# TCA_LP_FILTER.net
KiCad netlist of a schematic drawn in Altium Designer
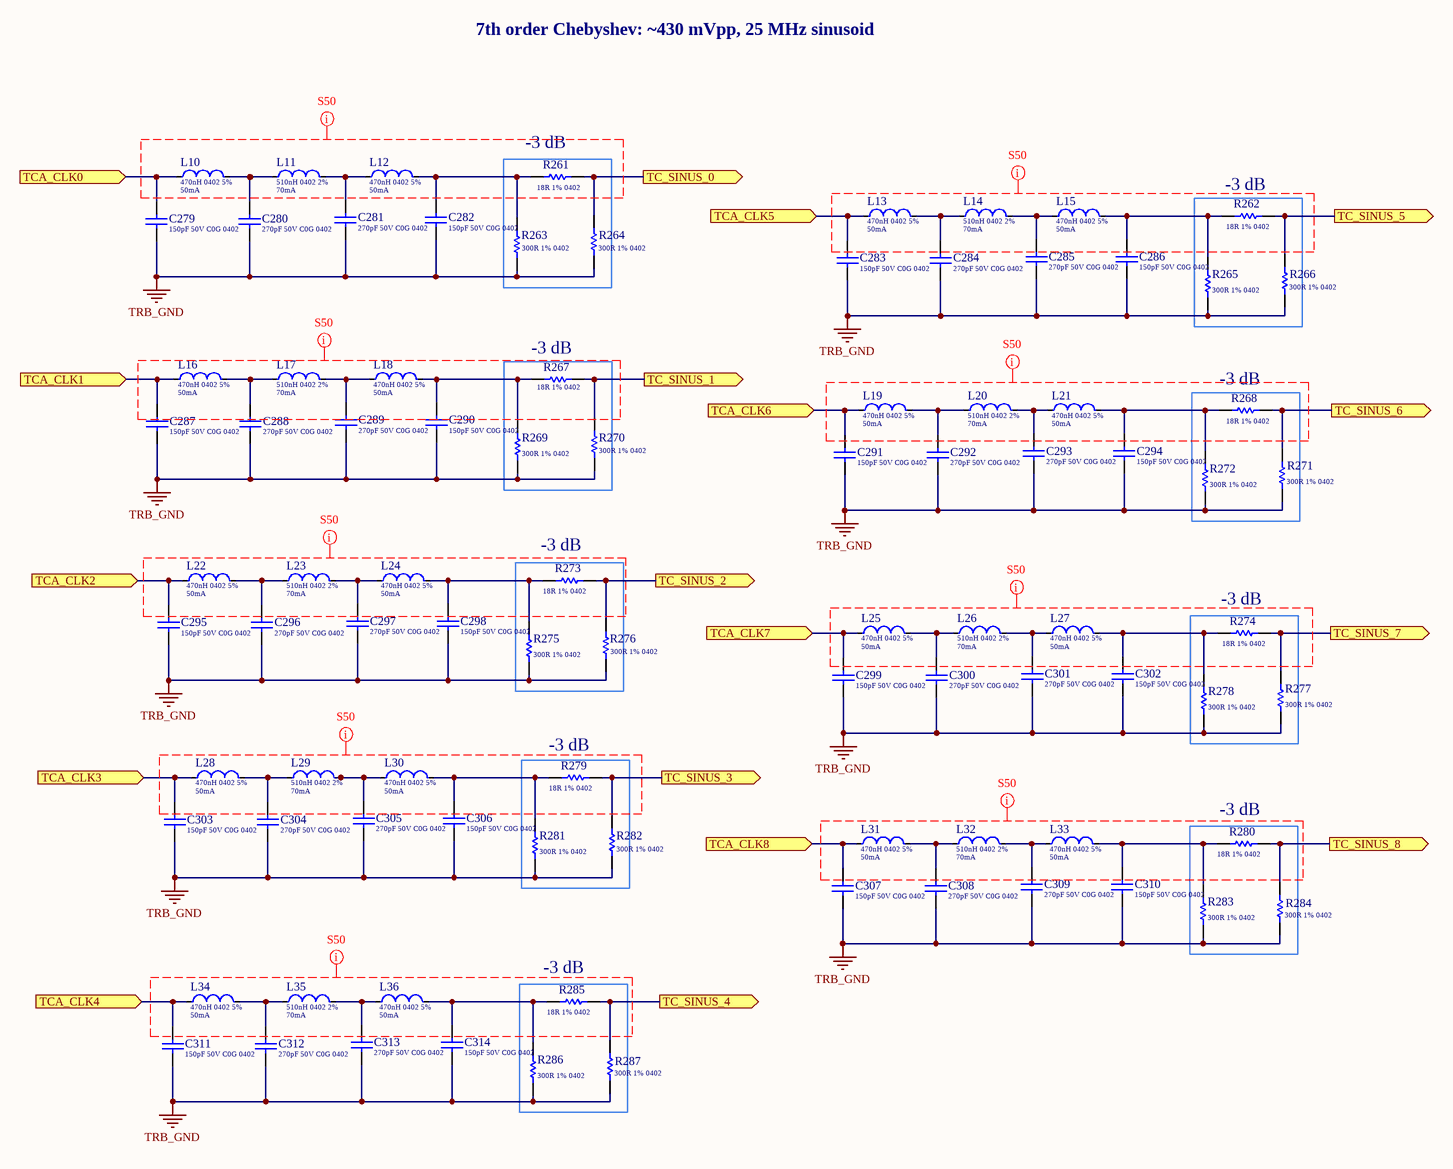
[diagram p0: TCA_LP_FILTER.SchDoc]

(export (version "E")
  (design (tool "Eeschema 10.0.6"))
  (components
    (comp (ref "C279")
      (value "Cap_TDK_CGA2B2C0G2A151J050BE_150pF")
      (footprint "Cap_TDK_CGA2B2C0G2A151J050BE_150pF")
      (description "CAP 150pF 50V C0G ±1% 0402 (1000 Metric) Thickness 1mm SMD")
      (fields (field (name "CAPACITANCE") "150pF 50V C0G 0402"))
      (libsource (lib "Cap_TDK_CGA2B2C0G2A151J050BE_150pF") (part "Cap_TDK_CGA2B2C0G2A151J050BE_150pF"))
    )
    (comp (ref "C280")
      (value "Cap_Murata_GCM1555C1H271FA16D_270pF")
      (footprint "Cap_Murata_GCM1555C1H271FA16D_270pF")
      (description "CAP 270pF 50V C0G ±1% 0402")
      (fields (field (name "CAPACITANCE") "270pF 50V C0G 0402"))
      (libsource (lib "Cap_Murata_GCM1555C1H271FA16D_270pF") (part "Cap_Murata_GCM1555C1H271FA16D_270pF"))
    )
    (comp (ref "C281")
      (value "Cap_Murata_GCM1555C1H271FA16D_270pF")
      (footprint "Cap_Murata_GCM1555C1H271FA16D_270pF")
      (description "CAP 270pF 50V C0G ±1% 0402")
      (fields (field (name "CAPACITANCE") "270pF 50V C0G 0402"))
      (libsource (lib "Cap_Murata_GCM1555C1H271FA16D_270pF") (part "Cap_Murata_GCM1555C1H271FA16D_270pF"))
    )
    (comp (ref "C282")
      (value "Cap_TDK_CGA2B2C0G2A151J050BE_150pF")
      (footprint "Cap_TDK_CGA2B2C0G2A151J050BE_150pF")
      (description "CAP 150pF 50V C0G ±1% 0402 (1000 Metric) Thickness 1mm SMD")
      (fields (field (name "CAPACITANCE") "150pF 50V C0G 0402"))
      (libsource (lib "Cap_TDK_CGA2B2C0G2A151J050BE_150pF") (part "Cap_TDK_CGA2B2C0G2A151J050BE_150pF"))
    )
    (comp (ref "C283")
      (value "Cap_TDK_CGA2B2C0G2A151J050BE_150pF")
      (footprint "Cap_TDK_CGA2B2C0G2A151J050BE_150pF")
      (description "CAP 150pF 50V C0G ±1% 0402 (1000 Metric) Thickness 1mm SMD")
      (fields (field (name "CAPACITANCE") "150pF 50V C0G 0402"))
      (libsource (lib "Cap_TDK_CGA2B2C0G2A151J050BE_150pF") (part "Cap_TDK_CGA2B2C0G2A151J050BE_150pF"))
    )
    (comp (ref "C284")
      (value "Cap_Murata_GCM1555C1H271FA16D_270pF")
      (footprint "Cap_Murata_GCM1555C1H271FA16D_270pF")
      (description "CAP 270pF 50V C0G ±1% 0402")
      (fields (field (name "CAPACITANCE") "270pF 50V C0G 0402"))
      (libsource (lib "Cap_Murata_GCM1555C1H271FA16D_270pF") (part "Cap_Murata_GCM1555C1H271FA16D_270pF"))
    )
    (comp (ref "C285")
      (value "Cap_Murata_GCM1555C1H271FA16D_270pF")
      (footprint "Cap_Murata_GCM1555C1H271FA16D_270pF")
      (description "CAP 270pF 50V C0G ±1% 0402")
      (fields (field (name "CAPACITANCE") "270pF 50V C0G 0402"))
      (libsource (lib "Cap_Murata_GCM1555C1H271FA16D_270pF") (part "Cap_Murata_GCM1555C1H271FA16D_270pF"))
    )
    (comp (ref "C286")
      (value "Cap_TDK_CGA2B2C0G2A151J050BE_150pF")
      (footprint "Cap_TDK_CGA2B2C0G2A151J050BE_150pF")
      (description "CAP 150pF 50V C0G ±1% 0402 (1000 Metric) Thickness 1mm SMD")
      (fields (field (name "CAPACITANCE") "150pF 50V C0G 0402"))
      (libsource (lib "Cap_TDK_CGA2B2C0G2A151J050BE_150pF") (part "Cap_TDK_CGA2B2C0G2A151J050BE_150pF"))
    )
    (comp (ref "C287")
      (value "Cap_TDK_CGA2B2C0G2A151J050BE_150pF")
      (footprint "Cap_TDK_CGA2B2C0G2A151J050BE_150pF")
      (description "CAP 150pF 50V C0G ±1% 0402 (1000 Metric) Thickness 1mm SMD")
      (fields (field (name "CAPACITANCE") "150pF 50V C0G 0402"))
      (libsource (lib "Cap_TDK_CGA2B2C0G2A151J050BE_150pF") (part "Cap_TDK_CGA2B2C0G2A151J050BE_150pF"))
    )
    (comp (ref "C288")
      (value "Cap_Murata_GCM1555C1H271FA16D_270pF")
      (footprint "Cap_Murata_GCM1555C1H271FA16D_270pF")
      (description "CAP 270pF 50V C0G ±1% 0402")
      (fields (field (name "CAPACITANCE") "270pF 50V C0G 0402"))
      (libsource (lib "Cap_Murata_GCM1555C1H271FA16D_270pF") (part "Cap_Murata_GCM1555C1H271FA16D_270pF"))
    )
    (comp (ref "C289")
      (value "Cap_Murata_GCM1555C1H271FA16D_270pF")
      (footprint "Cap_Murata_GCM1555C1H271FA16D_270pF")
      (description "CAP 270pF 50V C0G ±1% 0402")
      (fields (field (name "CAPACITANCE") "270pF 50V C0G 0402"))
      (libsource (lib "Cap_Murata_GCM1555C1H271FA16D_270pF") (part "Cap_Murata_GCM1555C1H271FA16D_270pF"))
    )
    (comp (ref "C290")
      (value "Cap_TDK_CGA2B2C0G2A151J050BE_150pF")
      (footprint "Cap_TDK_CGA2B2C0G2A151J050BE_150pF")
      (description "CAP 150pF 50V C0G ±1% 0402 (1000 Metric) Thickness 1mm SMD")
      (fields (field (name "CAPACITANCE") "150pF 50V C0G 0402"))
      (libsource (lib "Cap_TDK_CGA2B2C0G2A151J050BE_150pF") (part "Cap_TDK_CGA2B2C0G2A151J050BE_150pF"))
    )
    (comp (ref "C291")
      (value "Cap_TDK_CGA2B2C0G2A151J050BE_150pF")
      (footprint "Cap_TDK_CGA2B2C0G2A151J050BE_150pF")
      (description "CAP 150pF 50V C0G ±1% 0402 (1000 Metric) Thickness 1mm SMD")
      (fields (field (name "CAPACITANCE") "150pF 50V C0G 0402"))
      (libsource (lib "Cap_TDK_CGA2B2C0G2A151J050BE_150pF") (part "Cap_TDK_CGA2B2C0G2A151J050BE_150pF"))
    )
    (comp (ref "C292")
      (value "Cap_Murata_GCM1555C1H271FA16D_270pF")
      (footprint "Cap_Murata_GCM1555C1H271FA16D_270pF")
      (description "CAP 270pF 50V C0G ±1% 0402")
      (fields (field (name "CAPACITANCE") "270pF 50V C0G 0402"))
      (libsource (lib "Cap_Murata_GCM1555C1H271FA16D_270pF") (part "Cap_Murata_GCM1555C1H271FA16D_270pF"))
    )
    (comp (ref "C293")
      (value "Cap_Murata_GCM1555C1H271FA16D_270pF")
      (footprint "Cap_Murata_GCM1555C1H271FA16D_270pF")
      (description "CAP 270pF 50V C0G ±1% 0402")
      (fields (field (name "CAPACITANCE") "270pF 50V C0G 0402"))
      (libsource (lib "Cap_Murata_GCM1555C1H271FA16D_270pF") (part "Cap_Murata_GCM1555C1H271FA16D_270pF"))
    )
    (comp (ref "C294")
      (value "Cap_TDK_CGA2B2C0G2A151J050BE_150pF")
      (footprint "Cap_TDK_CGA2B2C0G2A151J050BE_150pF")
      (description "CAP 150pF 50V C0G ±1% 0402 (1000 Metric) Thickness 1mm SMD")
      (fields (field (name "CAPACITANCE") "150pF 50V C0G 0402"))
      (libsource (lib "Cap_TDK_CGA2B2C0G2A151J050BE_150pF") (part "Cap_TDK_CGA2B2C0G2A151J050BE_150pF"))
    )
    (comp (ref "C295")
      (value "Cap_TDK_CGA2B2C0G2A151J050BE_150pF")
      (footprint "Cap_TDK_CGA2B2C0G2A151J050BE_150pF")
      (description "CAP 150pF 50V C0G ±1% 0402 (1000 Metric) Thickness 1mm SMD")
      (fields (field (name "CAPACITANCE") "150pF 50V C0G 0402"))
      (libsource (lib "Cap_TDK_CGA2B2C0G2A151J050BE_150pF") (part "Cap_TDK_CGA2B2C0G2A151J050BE_150pF"))
    )
    (comp (ref "C296")
      (value "Cap_Murata_GCM1555C1H271FA16D_270pF")
      (footprint "Cap_Murata_GCM1555C1H271FA16D_270pF")
      (description "CAP 270pF 50V C0G ±1% 0402")
      (fields (field (name "CAPACITANCE") "270pF 50V C0G 0402"))
      (libsource (lib "Cap_Murata_GCM1555C1H271FA16D_270pF") (part "Cap_Murata_GCM1555C1H271FA16D_270pF"))
    )
    (comp (ref "C297")
      (value "Cap_Murata_GCM1555C1H271FA16D_270pF")
      (footprint "Cap_Murata_GCM1555C1H271FA16D_270pF")
      (description "CAP 270pF 50V C0G ±1% 0402")
      (fields (field (name "CAPACITANCE") "270pF 50V C0G 0402"))
      (libsource (lib "Cap_Murata_GCM1555C1H271FA16D_270pF") (part "Cap_Murata_GCM1555C1H271FA16D_270pF"))
    )
    (comp (ref "C298")
      (value "Cap_TDK_CGA2B2C0G2A151J050BE_150pF")
      (footprint "Cap_TDK_CGA2B2C0G2A151J050BE_150pF")
      (description "CAP 150pF 50V C0G ±1% 0402 (1000 Metric) Thickness 1mm SMD")
      (fields (field (name "CAPACITANCE") "150pF 50V C0G 0402"))
      (libsource (lib "Cap_TDK_CGA2B2C0G2A151J050BE_150pF") (part "Cap_TDK_CGA2B2C0G2A151J050BE_150pF"))
    )
    (comp (ref "C299")
      (value "Cap_TDK_CGA2B2C0G2A151J050BE_150pF")
      (footprint "Cap_TDK_CGA2B2C0G2A151J050BE_150pF")
      (description "CAP 150pF 50V C0G ±1% 0402 (1000 Metric) Thickness 1mm SMD")
      (fields (field (name "CAPACITANCE") "150pF 50V C0G 0402"))
      (libsource (lib "Cap_TDK_CGA2B2C0G2A151J050BE_150pF") (part "Cap_TDK_CGA2B2C0G2A151J050BE_150pF"))
    )
    (comp (ref "C300")
      (value "Cap_Murata_GCM1555C1H271FA16D_270pF")
      (footprint "Cap_Murata_GCM1555C1H271FA16D_270pF")
      (description "CAP 270pF 50V C0G ±1% 0402")
      (fields (field (name "CAPACITANCE") "270pF 50V C0G 0402"))
      (libsource (lib "Cap_Murata_GCM1555C1H271FA16D_270pF") (part "Cap_Murata_GCM1555C1H271FA16D_270pF"))
    )
    (comp (ref "C301")
      (value "Cap_Murata_GCM1555C1H271FA16D_270pF")
      (footprint "Cap_Murata_GCM1555C1H271FA16D_270pF")
      (description "CAP 270pF 50V C0G ±1% 0402")
      (fields (field (name "CAPACITANCE") "270pF 50V C0G 0402"))
      (libsource (lib "Cap_Murata_GCM1555C1H271FA16D_270pF") (part "Cap_Murata_GCM1555C1H271FA16D_270pF"))
    )
    (comp (ref "C302")
      (value "Cap_TDK_CGA2B2C0G2A151J050BE_150pF")
      (footprint "Cap_TDK_CGA2B2C0G2A151J050BE_150pF")
      (description "CAP 150pF 50V C0G ±1% 0402 (1000 Metric) Thickness 1mm SMD")
      (fields (field (name "CAPACITANCE") "150pF 50V C0G 0402"))
      (libsource (lib "Cap_TDK_CGA2B2C0G2A151J050BE_150pF") (part "Cap_TDK_CGA2B2C0G2A151J050BE_150pF"))
    )
    (comp (ref "C303")
      (value "Cap_TDK_CGA2B2C0G2A151J050BE_150pF")
      (footprint "Cap_TDK_CGA2B2C0G2A151J050BE_150pF")
      (description "CAP 150pF 50V C0G ±1% 0402 (1000 Metric) Thickness 1mm SMD")
      (fields (field (name "CAPACITANCE") "150pF 50V C0G 0402"))
      (libsource (lib "Cap_TDK_CGA2B2C0G2A151J050BE_150pF") (part "Cap_TDK_CGA2B2C0G2A151J050BE_150pF"))
    )
    (comp (ref "C304")
      (value "Cap_Murata_GCM1555C1H271FA16D_270pF")
      (footprint "Cap_Murata_GCM1555C1H271FA16D_270pF")
      (description "CAP 270pF 50V C0G ±1% 0402")
      (fields (field (name "CAPACITANCE") "270pF 50V C0G 0402"))
      (libsource (lib "Cap_Murata_GCM1555C1H271FA16D_270pF") (part "Cap_Murata_GCM1555C1H271FA16D_270pF"))
    )
    (comp (ref "C305")
      (value "Cap_Murata_GCM1555C1H271FA16D_270pF")
      (footprint "Cap_Murata_GCM1555C1H271FA16D_270pF")
      (description "CAP 270pF 50V C0G ±1% 0402")
      (fields (field (name "CAPACITANCE") "270pF 50V C0G 0402"))
      (libsource (lib "Cap_Murata_GCM1555C1H271FA16D_270pF") (part "Cap_Murata_GCM1555C1H271FA16D_270pF"))
    )
    (comp (ref "C306")
      (value "Cap_TDK_CGA2B2C0G2A151J050BE_150pF")
      (footprint "Cap_TDK_CGA2B2C0G2A151J050BE_150pF")
      (description "CAP 150pF 50V C0G ±1% 0402 (1000 Metric) Thickness 1mm SMD")
      (fields (field (name "CAPACITANCE") "150pF 50V C0G 0402"))
      (libsource (lib "Cap_TDK_CGA2B2C0G2A151J050BE_150pF") (part "Cap_TDK_CGA2B2C0G2A151J050BE_150pF"))
    )
    (comp (ref "C307")
      (value "Cap_TDK_CGA2B2C0G2A151J050BE_150pF")
      (footprint "Cap_TDK_CGA2B2C0G2A151J050BE_150pF")
      (description "CAP 150pF 50V C0G ±1% 0402 (1000 Metric) Thickness 1mm SMD")
      (fields (field (name "CAPACITANCE") "150pF 50V C0G 0402"))
      (libsource (lib "Cap_TDK_CGA2B2C0G2A151J050BE_150pF") (part "Cap_TDK_CGA2B2C0G2A151J050BE_150pF"))
    )
    (comp (ref "C308")
      (value "Cap_Murata_GCM1555C1H271FA16D_270pF")
      (footprint "Cap_Murata_GCM1555C1H271FA16D_270pF")
      (description "CAP 270pF 50V C0G ±1% 0402")
      (fields (field (name "CAPACITANCE") "270pF 50V C0G 0402"))
      (libsource (lib "Cap_Murata_GCM1555C1H271FA16D_270pF") (part "Cap_Murata_GCM1555C1H271FA16D_270pF"))
    )
    (comp (ref "C309")
      (value "Cap_Murata_GCM1555C1H271FA16D_270pF")
      (footprint "Cap_Murata_GCM1555C1H271FA16D_270pF")
      (description "CAP 270pF 50V C0G ±1% 0402")
      (fields (field (name "CAPACITANCE") "270pF 50V C0G 0402"))
      (libsource (lib "Cap_Murata_GCM1555C1H271FA16D_270pF") (part "Cap_Murata_GCM1555C1H271FA16D_270pF"))
    )
    (comp (ref "C310")
      (value "Cap_TDK_CGA2B2C0G2A151J050BE_150pF")
      (footprint "Cap_TDK_CGA2B2C0G2A151J050BE_150pF")
      (description "CAP 150pF 50V C0G ±1% 0402 (1000 Metric) Thickness 1mm SMD")
      (fields (field (name "CAPACITANCE") "150pF 50V C0G 0402"))
      (libsource (lib "Cap_TDK_CGA2B2C0G2A151J050BE_150pF") (part "Cap_TDK_CGA2B2C0G2A151J050BE_150pF"))
    )
    (comp (ref "C311")
      (value "Cap_TDK_CGA2B2C0G2A151J050BE_150pF")
      (footprint "Cap_TDK_CGA2B2C0G2A151J050BE_150pF")
      (description "CAP 150pF 50V C0G ±1% 0402 (1000 Metric) Thickness 1mm SMD")
      (fields (field (name "CAPACITANCE") "150pF 50V C0G 0402"))
      (libsource (lib "Cap_TDK_CGA2B2C0G2A151J050BE_150pF") (part "Cap_TDK_CGA2B2C0G2A151J050BE_150pF"))
    )
    (comp (ref "C312")
      (value "Cap_Murata_GCM1555C1H271FA16D_270pF")
      (footprint "Cap_Murata_GCM1555C1H271FA16D_270pF")
      (description "CAP 270pF 50V C0G ±1% 0402")
      (fields (field (name "CAPACITANCE") "270pF 50V C0G 0402"))
      (libsource (lib "Cap_Murata_GCM1555C1H271FA16D_270pF") (part "Cap_Murata_GCM1555C1H271FA16D_270pF"))
    )
    (comp (ref "C313")
      (value "Cap_Murata_GCM1555C1H271FA16D_270pF")
      (footprint "Cap_Murata_GCM1555C1H271FA16D_270pF")
      (description "CAP 270pF 50V C0G ±1% 0402")
      (fields (field (name "CAPACITANCE") "270pF 50V C0G 0402"))
      (libsource (lib "Cap_Murata_GCM1555C1H271FA16D_270pF") (part "Cap_Murata_GCM1555C1H271FA16D_270pF"))
    )
    (comp (ref "C314")
      (value "Cap_TDK_CGA2B2C0G2A151J050BE_150pF")
      (footprint "Cap_TDK_CGA2B2C0G2A151J050BE_150pF")
      (description "CAP 150pF 50V C0G ±1% 0402 (1000 Metric) Thickness 1mm SMD")
      (fields (field (name "CAPACITANCE") "150pF 50V C0G 0402"))
      (libsource (lib "Cap_TDK_CGA2B2C0G2A151J050BE_150pF") (part "Cap_TDK_CGA2B2C0G2A151J050BE_150pF"))
    )
    (comp (ref "L10")
      (value "470nH 0402 5%")
      (footprint "TDK_MLF1005GR47JT000_0")
      (description "IND 470nH Shielded Multilayer Inductor 50mA 420 mOhm Max 0402 (1005 Metric)")
      (fields
        (field (name "PART NUMBER") "MLF1005GR47JT000")
        (field (name "MANUFACTURER") "TDK")
        (field (name "CURRENT RATING") "50mA")
      )
      (libsource (lib "Ind_TDK_MLF1005GR47JT000_470nH") (part "Ind_TDK_MLF1005GR47JT000"))
    )
    (comp (ref "L11")
      (value "510nH 0402 2%")
      (footprint "TDK_MHQ1005PR51GT000_0")
      (description "IND 510nH Shielded Multilayer Inductor 70mA 10.2 Ohm Max 0402 (1005 Metric)")
      (fields
        (field (name "PART NUMBER") "MHQ1005PR51GT000")
        (field (name "MANUFACTURER") "TDK")
        (field (name "CURRENT RATING") "70mA")
      )
      (libsource (lib "Ind_TDK_MHQ1005PR51GT000_510nH") (part "Ind_TDK_MHQ1005PR51GT000"))
    )
    (comp (ref "L12")
      (value "470nH 0402 5%")
      (footprint "TDK_MLF1005GR47JT000_0")
      (description "IND 470nH Shielded Multilayer Inductor 50mA 420 mOhm Max 0402 (1005 Metric)")
      (fields
        (field (name "PART NUMBER") "MLF1005GR47JT000")
        (field (name "MANUFACTURER") "TDK")
        (field (name "CURRENT RATING") "50mA")
      )
      (libsource (lib "Ind_TDK_MLF1005GR47JT000_470nH") (part "Ind_TDK_MLF1005GR47JT000"))
    )
    (comp (ref "L13")
      (value "470nH 0402 5%")
      (footprint "TDK_MLF1005GR47JT000_0")
      (description "IND 470nH Shielded Multilayer Inductor 50mA 420 mOhm Max 0402 (1005 Metric)")
      (fields
        (field (name "PART NUMBER") "MLF1005GR47JT000")
        (field (name "MANUFACTURER") "TDK")
        (field (name "CURRENT RATING") "50mA")
      )
      (libsource (lib "Ind_TDK_MLF1005GR47JT000_470nH") (part "Ind_TDK_MLF1005GR47JT000"))
    )
    (comp (ref "L14")
      (value "510nH 0402 2%")
      (footprint "TDK_MHQ1005PR51GT000_0")
      (description "IND 510nH Shielded Multilayer Inductor 70mA 10.2 Ohm Max 0402 (1005 Metric)")
      (fields
        (field (name "PART NUMBER") "MHQ1005PR51GT000")
        (field (name "MANUFACTURER") "TDK")
        (field (name "CURRENT RATING") "70mA")
      )
      (libsource (lib "Ind_TDK_MHQ1005PR51GT000_510nH") (part "Ind_TDK_MHQ1005PR51GT000"))
    )
    (comp (ref "L15")
      (value "470nH 0402 5%")
      (footprint "TDK_MLF1005GR47JT000_0")
      (description "IND 470nH Shielded Multilayer Inductor 50mA 420 mOhm Max 0402 (1005 Metric)")
      (fields
        (field (name "PART NUMBER") "MLF1005GR47JT000")
        (field (name "MANUFACTURER") "TDK")
        (field (name "CURRENT RATING") "50mA")
      )
      (libsource (lib "Ind_TDK_MLF1005GR47JT000_470nH") (part "Ind_TDK_MLF1005GR47JT000"))
    )
    (comp (ref "L16")
      (value "470nH 0402 5%")
      (footprint "TDK_MLF1005GR47JT000_0")
      (description "IND 470nH Shielded Multilayer Inductor 50mA 420 mOhm Max 0402 (1005 Metric)")
      (fields
        (field (name "PART NUMBER") "MLF1005GR47JT000")
        (field (name "MANUFACTURER") "TDK")
        (field (name "CURRENT RATING") "50mA")
      )
      (libsource (lib "Ind_TDK_MLF1005GR47JT000_470nH") (part "Ind_TDK_MLF1005GR47JT000"))
    )
    (comp (ref "L17")
      (value "510nH 0402 2%")
      (footprint "TDK_MHQ1005PR51GT000_0")
      (description "IND 510nH Shielded Multilayer Inductor 70mA 10.2 Ohm Max 0402 (1005 Metric)")
      (fields
        (field (name "PART NUMBER") "MHQ1005PR51GT000")
        (field (name "MANUFACTURER") "TDK")
        (field (name "CURRENT RATING") "70mA")
      )
      (libsource (lib "Ind_TDK_MHQ1005PR51GT000_510nH") (part "Ind_TDK_MHQ1005PR51GT000"))
    )
    (comp (ref "L18")
      (value "470nH 0402 5%")
      (footprint "TDK_MLF1005GR47JT000_0")
      (description "IND 470nH Shielded Multilayer Inductor 50mA 420 mOhm Max 0402 (1005 Metric)")
      (fields
        (field (name "PART NUMBER") "MLF1005GR47JT000")
        (field (name "MANUFACTURER") "TDK")
        (field (name "CURRENT RATING") "50mA")
      )
      (libsource (lib "Ind_TDK_MLF1005GR47JT000_470nH") (part "Ind_TDK_MLF1005GR47JT000"))
    )
    (comp (ref "L19")
      (value "470nH 0402 5%")
      (footprint "TDK_MLF1005GR47JT000_0")
      (description "IND 470nH Shielded Multilayer Inductor 50mA 420 mOhm Max 0402 (1005 Metric)")
      (fields
        (field (name "PART NUMBER") "MLF1005GR47JT000")
        (field (name "MANUFACTURER") "TDK")
        (field (name "CURRENT RATING") "50mA")
      )
      (libsource (lib "Ind_TDK_MLF1005GR47JT000_470nH") (part "Ind_TDK_MLF1005GR47JT000"))
    )
    (comp (ref "L20")
      (value "510nH 0402 2%")
      (footprint "TDK_MHQ1005PR51GT000_0")
      (description "IND 510nH Shielded Multilayer Inductor 70mA 10.2 Ohm Max 0402 (1005 Metric)")
      (fields
        (field (name "PART NUMBER") "MHQ1005PR51GT000")
        (field (name "MANUFACTURER") "TDK")
        (field (name "CURRENT RATING") "70mA")
      )
      (libsource (lib "Ind_TDK_MHQ1005PR51GT000_510nH") (part "Ind_TDK_MHQ1005PR51GT000"))
    )
    (comp (ref "L21")
      (value "470nH 0402 5%")
      (footprint "TDK_MLF1005GR47JT000_0")
      (description "IND 470nH Shielded Multilayer Inductor 50mA 420 mOhm Max 0402 (1005 Metric)")
      (fields
        (field (name "PART NUMBER") "MLF1005GR47JT000")
        (field (name "MANUFACTURER") "TDK")
        (field (name "CURRENT RATING") "50mA")
      )
      (libsource (lib "Ind_TDK_MLF1005GR47JT000_470nH") (part "Ind_TDK_MLF1005GR47JT000"))
    )
    (comp (ref "L22")
      (value "470nH 0402 5%")
      (footprint "TDK_MLF1005GR47JT000_0")
      (description "IND 470nH Shielded Multilayer Inductor 50mA 420 mOhm Max 0402 (1005 Metric)")
      (fields
        (field (name "PART NUMBER") "MLF1005GR47JT000")
        (field (name "MANUFACTURER") "TDK")
        (field (name "CURRENT RATING") "50mA")
      )
      (libsource (lib "Ind_TDK_MLF1005GR47JT000_470nH") (part "Ind_TDK_MLF1005GR47JT000"))
    )
    (comp (ref "L23")
      (value "510nH 0402 2%")
      (footprint "TDK_MHQ1005PR51GT000_0")
      (description "IND 510nH Shielded Multilayer Inductor 70mA 10.2 Ohm Max 0402 (1005 Metric)")
      (fields
        (field (name "PART NUMBER") "MHQ1005PR51GT000")
        (field (name "MANUFACTURER") "TDK")
        (field (name "CURRENT RATING") "70mA")
      )
      (libsource (lib "Ind_TDK_MHQ1005PR51GT000_510nH") (part "Ind_TDK_MHQ1005PR51GT000"))
    )
    (comp (ref "L24")
      (value "470nH 0402 5%")
      (footprint "TDK_MLF1005GR47JT000_0")
      (description "IND 470nH Shielded Multilayer Inductor 50mA 420 mOhm Max 0402 (1005 Metric)")
      (fields
        (field (name "PART NUMBER") "MLF1005GR47JT000")
        (field (name "MANUFACTURER") "TDK")
        (field (name "CURRENT RATING") "50mA")
      )
      (libsource (lib "Ind_TDK_MLF1005GR47JT000_470nH") (part "Ind_TDK_MLF1005GR47JT000"))
    )
    (comp (ref "L25")
      (value "470nH 0402 5%")
      (footprint "TDK_MLF1005GR47JT000_0")
      (description "IND 470nH Shielded Multilayer Inductor 50mA 420 mOhm Max 0402 (1005 Metric)")
      (fields
        (field (name "PART NUMBER") "MLF1005GR47JT000")
        (field (name "MANUFACTURER") "TDK")
        (field (name "CURRENT RATING") "50mA")
      )
      (libsource (lib "Ind_TDK_MLF1005GR47JT000_470nH") (part "Ind_TDK_MLF1005GR47JT000"))
    )
    (comp (ref "L26")
      (value "510nH 0402 2%")
      (footprint "TDK_MHQ1005PR51GT000_0")
      (description "IND 510nH Shielded Multilayer Inductor 70mA 10.2 Ohm Max 0402 (1005 Metric)")
      (fields
        (field (name "PART NUMBER") "MHQ1005PR51GT000")
        (field (name "MANUFACTURER") "TDK")
        (field (name "CURRENT RATING") "70mA")
      )
      (libsource (lib "Ind_TDK_MHQ1005PR51GT000_510nH") (part "Ind_TDK_MHQ1005PR51GT000"))
    )
    (comp (ref "L27")
      (value "470nH 0402 5%")
      (footprint "TDK_MLF1005GR47JT000_0")
      (description "IND 470nH Shielded Multilayer Inductor 50mA 420 mOhm Max 0402 (1005 Metric)")
      (fields
        (field (name "PART NUMBER") "MLF1005GR47JT000")
        (field (name "MANUFACTURER") "TDK")
        (field (name "CURRENT RATING") "50mA")
      )
      (libsource (lib "Ind_TDK_MLF1005GR47JT000_470nH") (part "Ind_TDK_MLF1005GR47JT000"))
    )
    (comp (ref "L28")
      (value "470nH 0402 5%")
      (footprint "TDK_MLF1005GR47JT000_0")
      (description "IND 470nH Shielded Multilayer Inductor 50mA 420 mOhm Max 0402 (1005 Metric)")
      (fields
        (field (name "PART NUMBER") "MLF1005GR47JT000")
        (field (name "MANUFACTURER") "TDK")
        (field (name "CURRENT RATING") "50mA")
      )
      (libsource (lib "Ind_TDK_MLF1005GR47JT000_470nH") (part "Ind_TDK_MLF1005GR47JT000"))
    )
    (comp (ref "L29")
      (value "510nH 0402 2%")
      (footprint "TDK_MHQ1005PR51GT000_0")
      (description "IND 510nH Shielded Multilayer Inductor 70mA 10.2 Ohm Max 0402 (1005 Metric)")
      (fields
        (field (name "PART NUMBER") "MHQ1005PR51GT000")
        (field (name "MANUFACTURER") "TDK")
        (field (name "CURRENT RATING") "70mA")
      )
      (libsource (lib "Ind_TDK_MHQ1005PR51GT000_510nH") (part "Ind_TDK_MHQ1005PR51GT000"))
    )
    (comp (ref "L30")
      (value "470nH 0402 5%")
      (footprint "TDK_MLF1005GR47JT000_0")
      (description "IND 470nH Shielded Multilayer Inductor 50mA 420 mOhm Max 0402 (1005 Metric)")
      (fields
        (field (name "PART NUMBER") "MLF1005GR47JT000")
        (field (name "MANUFACTURER") "TDK")
        (field (name "CURRENT RATING") "50mA")
      )
      (libsource (lib "Ind_TDK_MLF1005GR47JT000_470nH") (part "Ind_TDK_MLF1005GR47JT000"))
    )
    (comp (ref "L31")
      (value "470nH 0402 5%")
      (footprint "TDK_MLF1005GR47JT000_0")
      (description "IND 470nH Shielded Multilayer Inductor 50mA 420 mOhm Max 0402 (1005 Metric)")
      (fields
        (field (name "PART NUMBER") "MLF1005GR47JT000")
        (field (name "MANUFACTURER") "TDK")
        (field (name "CURRENT RATING") "50mA")
      )
      (libsource (lib "Ind_TDK_MLF1005GR47JT000_470nH") (part "Ind_TDK_MLF1005GR47JT000"))
    )
    (comp (ref "L32")
      (value "510nH 0402 2%")
      (footprint "TDK_MHQ1005PR51GT000_0")
      (description "IND 510nH Shielded Multilayer Inductor 70mA 10.2 Ohm Max 0402 (1005 Metric)")
      (fields
        (field (name "PART NUMBER") "MHQ1005PR51GT000")
        (field (name "MANUFACTURER") "TDK")
        (field (name "CURRENT RATING") "70mA")
      )
      (libsource (lib "Ind_TDK_MHQ1005PR51GT000_510nH") (part "Ind_TDK_MHQ1005PR51GT000"))
    )
    (comp (ref "L33")
      (value "470nH 0402 5%")
      (footprint "TDK_MLF1005GR47JT000_0")
      (description "IND 470nH Shielded Multilayer Inductor 50mA 420 mOhm Max 0402 (1005 Metric)")
      (fields
        (field (name "PART NUMBER") "MLF1005GR47JT000")
        (field (name "MANUFACTURER") "TDK")
        (field (name "CURRENT RATING") "50mA")
      )
      (libsource (lib "Ind_TDK_MLF1005GR47JT000_470nH") (part "Ind_TDK_MLF1005GR47JT000"))
    )
    (comp (ref "L34")
      (value "470nH 0402 5%")
      (footprint "TDK_MLF1005GR47JT000_0")
      (description "IND 470nH Shielded Multilayer Inductor 50mA 420 mOhm Max 0402 (1005 Metric)")
      (fields
        (field (name "PART NUMBER") "MLF1005GR47JT000")
        (field (name "MANUFACTURER") "TDK")
        (field (name "CURRENT RATING") "50mA")
      )
      (libsource (lib "Ind_TDK_MLF1005GR47JT000_470nH") (part "Ind_TDK_MLF1005GR47JT000"))
    )
    (comp (ref "L35")
      (value "510nH 0402 2%")
      (footprint "TDK_MHQ1005PR51GT000_0")
      (description "IND 510nH Shielded Multilayer Inductor 70mA 10.2 Ohm Max 0402 (1005 Metric)")
      (fields
        (field (name "PART NUMBER") "MHQ1005PR51GT000")
        (field (name "MANUFACTURER") "TDK")
        (field (name "CURRENT RATING") "70mA")
      )
      (libsource (lib "Ind_TDK_MHQ1005PR51GT000_510nH") (part "Ind_TDK_MHQ1005PR51GT000"))
    )
    (comp (ref "L36")
      (value "470nH 0402 5%")
      (footprint "TDK_MLF1005GR47JT000_0")
      (description "IND 470nH Shielded Multilayer Inductor 50mA 420 mOhm Max 0402 (1005 Metric)")
      (fields
        (field (name "PART NUMBER") "MLF1005GR47JT000")
        (field (name "MANUFACTURER") "TDK")
        (field (name "CURRENT RATING") "50mA")
      )
      (libsource (lib "Ind_TDK_MLF1005GR47JT000_470nH") (part "Ind_TDK_MLF1005GR47JT000"))
    )
    (comp (ref "R261")
      (value "18R 1% 0402")
      (footprint "RESC0402(1005)_L")
      (description "18R 0.063W 1% 0402 (1005 Metric)  SMD")
      (fields (field (name "TOLERANCE") "1 %") (field (name "POWER") "0.063 W"))
      (libsource (lib "Altium Content Vault") (part "RES"))
    )
    (comp (ref "R262")
      (value "18R 1% 0402")
      (footprint "RESC0402(1005)_L")
      (description "18R 0.063W 1% 0402 (1005 Metric)  SMD")
      (fields (field (name "TOLERANCE") "1 %") (field (name "POWER") "0.063 W"))
      (libsource (lib "Altium Content Vault") (part "RES"))
    )
    (comp (ref "R263")
      (value "300R 1% 0402")
      (footprint "RESC0402(1005)_L")
      (description "300R 0.063W 1% 0402 (1005 Metric)  SMD")
      (fields (field (name "TOLERANCE") "1 %") (field (name "POWER") "0.063 W"))
      (libsource (lib "Altium Content Vault") (part "RES"))
    )
    (comp (ref "R264")
      (value "300R 1% 0402")
      (footprint "RESC0402(1005)_L")
      (description "300R 0.063W 1% 0402 (1005 Metric)  SMD")
      (fields (field (name "TOLERANCE") "1 %") (field (name "POWER") "0.063 W"))
      (libsource (lib "Altium Content Vault") (part "RES"))
    )
    (comp (ref "R265")
      (value "300R 1% 0402")
      (footprint "RESC0402(1005)_L")
      (description "300R 0.063W 1% 0402 (1005 Metric)  SMD")
      (fields (field (name "TOLERANCE") "1 %") (field (name "POWER") "0.063 W"))
      (libsource (lib "Altium Content Vault") (part "RES"))
    )
    (comp (ref "R266")
      (value "300R 1% 0402")
      (footprint "RESC0402(1005)_L")
      (description "300R 0.063W 1% 0402 (1005 Metric)  SMD")
      (fields (field (name "TOLERANCE") "1 %") (field (name "POWER") "0.063 W"))
      (libsource (lib "Altium Content Vault") (part "RES"))
    )
    (comp (ref "R267")
      (value "18R 1% 0402")
      (footprint "RESC0402(1005)_L")
      (description "18R 0.063W 1% 0402 (1005 Metric)  SMD")
      (fields (field (name "TOLERANCE") "1 %") (field (name "POWER") "0.063 W"))
      (libsource (lib "Altium Content Vault") (part "RES"))
    )
    (comp (ref "R268")
      (value "18R 1% 0402")
      (footprint "RESC0402(1005)_L")
      (description "18R 0.063W 1% 0402 (1005 Metric)  SMD")
      (fields (field (name "TOLERANCE") "1 %") (field (name "POWER") "0.063 W"))
      (libsource (lib "Altium Content Vault") (part "RES"))
    )
    (comp (ref "R269")
      (value "300R 1% 0402")
      (footprint "RESC0402(1005)_L")
      (description "300R 0.063W 1% 0402 (1005 Metric)  SMD")
      (fields (field (name "TOLERANCE") "1 %") (field (name "POWER") "0.063 W"))
      (libsource (lib "Altium Content Vault") (part "RES"))
    )
    (comp (ref "R270")
      (value "300R 1% 0402")
      (footprint "RESC0402(1005)_L")
      (description "300R 0.063W 1% 0402 (1005 Metric)  SMD")
      (fields (field (name "TOLERANCE") "1 %") (field (name "POWER") "0.063 W"))
      (libsource (lib "Altium Content Vault") (part "RES"))
    )
    (comp (ref "R271")
      (value "300R 1% 0402")
      (footprint "RESC0402(1005)_L")
      (description "300R 0.063W 1% 0402 (1005 Metric)  SMD")
      (fields (field (name "TOLERANCE") "1 %") (field (name "POWER") "0.063 W"))
      (libsource (lib "Altium Content Vault") (part "RES"))
    )
    (comp (ref "R272")
      (value "300R 1% 0402")
      (footprint "RESC0402(1005)_L")
      (description "300R 0.063W 1% 0402 (1005 Metric)  SMD")
      (fields (field (name "TOLERANCE") "1 %") (field (name "POWER") "0.063 W"))
      (libsource (lib "Altium Content Vault") (part "RES"))
    )
    (comp (ref "R273")
      (value "18R 1% 0402")
      (footprint "RESC0402(1005)_L")
      (description "18R 0.063W 1% 0402 (1005 Metric)  SMD")
      (fields (field (name "TOLERANCE") "1 %") (field (name "POWER") "0.063 W"))
      (libsource (lib "Altium Content Vault") (part "RES"))
    )
    (comp (ref "R274")
      (value "18R 1% 0402")
      (footprint "RESC0402(1005)_L")
      (description "18R 0.063W 1% 0402 (1005 Metric)  SMD")
      (fields (field (name "TOLERANCE") "1 %") (field (name "POWER") "0.063 W"))
      (libsource (lib "Altium Content Vault") (part "RES"))
    )
    (comp (ref "R275")
      (value "300R 1% 0402")
      (footprint "RESC0402(1005)_L")
      (description "300R 0.063W 1% 0402 (1005 Metric)  SMD")
      (fields (field (name "TOLERANCE") "1 %") (field (name "POWER") "0.063 W"))
      (libsource (lib "Altium Content Vault") (part "RES"))
    )
    (comp (ref "R276")
      (value "300R 1% 0402")
      (footprint "RESC0402(1005)_L")
      (description "300R 0.063W 1% 0402 (1005 Metric)  SMD")
      (fields (field (name "TOLERANCE") "1 %") (field (name "POWER") "0.063 W"))
      (libsource (lib "Altium Content Vault") (part "RES"))
    )
    (comp (ref "R277")
      (value "300R 1% 0402")
      (footprint "RESC0402(1005)_L")
      (description "300R 0.063W 1% 0402 (1005 Metric)  SMD")
      (fields (field (name "TOLERANCE") "1 %") (field (name "POWER") "0.063 W"))
      (libsource (lib "Altium Content Vault") (part "RES"))
    )
    (comp (ref "R278")
      (value "300R 1% 0402")
      (footprint "RESC0402(1005)_L")
      (description "300R 0.063W 1% 0402 (1005 Metric)  SMD")
      (fields (field (name "TOLERANCE") "1 %") (field (name "POWER") "0.063 W"))
      (libsource (lib "Altium Content Vault") (part "RES"))
    )
    (comp (ref "R279")
      (value "18R 1% 0402")
      (footprint "RESC0402(1005)_L")
      (description "18R 0.063W 1% 0402 (1005 Metric)  SMD")
      (fields (field (name "TOLERANCE") "1 %") (field (name "POWER") "0.063 W"))
      (libsource (lib "Altium Content Vault") (part "RES"))
    )
    (comp (ref "R280")
      (value "18R 1% 0402")
      (footprint "RESC0402(1005)_L")
      (description "18R 0.063W 1% 0402 (1005 Metric)  SMD")
      (fields (field (name "TOLERANCE") "1 %") (field (name "POWER") "0.063 W"))
      (libsource (lib "Altium Content Vault") (part "RES"))
    )
    (comp (ref "R281")
      (value "300R 1% 0402")
      (footprint "RESC0402(1005)_L")
      (description "300R 0.063W 1% 0402 (1005 Metric)  SMD")
      (fields (field (name "TOLERANCE") "1 %") (field (name "POWER") "0.063 W"))
      (libsource (lib "Altium Content Vault") (part "RES"))
    )
    (comp (ref "R282")
      (value "300R 1% 0402")
      (footprint "RESC0402(1005)_L")
      (description "300R 0.063W 1% 0402 (1005 Metric)  SMD")
      (fields (field (name "TOLERANCE") "1 %") (field (name "POWER") "0.063 W"))
      (libsource (lib "Altium Content Vault") (part "RES"))
    )
    (comp (ref "R283")
      (value "300R 1% 0402")
      (footprint "RESC0402(1005)_L")
      (description "300R 0.063W 1% 0402 (1005 Metric)  SMD")
      (fields (field (name "TOLERANCE") "1 %") (field (name "POWER") "0.063 W"))
      (libsource (lib "Altium Content Vault") (part "RES"))
    )
    (comp (ref "R284")
      (value "300R 1% 0402")
      (footprint "RESC0402(1005)_L")
      (description "300R 0.063W 1% 0402 (1005 Metric)  SMD")
      (fields (field (name "TOLERANCE") "1 %") (field (name "POWER") "0.063 W"))
      (libsource (lib "Altium Content Vault") (part "RES"))
    )
    (comp (ref "R285")
      (value "18R 1% 0402")
      (footprint "RESC0402(1005)_L")
      (description "18R 0.063W 1% 0402 (1005 Metric)  SMD")
      (fields (field (name "TOLERANCE") "1 %") (field (name "POWER") "0.063 W"))
      (libsource (lib "Altium Content Vault") (part "RES"))
    )
    (comp (ref "R286")
      (value "300R 1% 0402")
      (footprint "RESC0402(1005)_L")
      (description "300R 0.063W 1% 0402 (1005 Metric)  SMD")
      (fields (field (name "TOLERANCE") "1 %") (field (name "POWER") "0.063 W"))
      (libsource (lib "Altium Content Vault") (part "RES"))
    )
    (comp (ref "R287")
      (value "300R 1% 0402")
      (footprint "RESC0402(1005)_L")
      (description "300R 0.063W 1% 0402 (1005 Metric)  SMD")
      (fields (field (name "TOLERANCE") "1 %") (field (name "POWER") "0.063 W"))
      (libsource (lib "Altium Content Vault") (part "RES"))
    )
  )
  (nets
    (net (code "1") (name "/TCA_CLK0") (class "Default")
      (node (ref "C279") (pin "2") (pinfunction "2_2") (pintype "passive"))
      (node (ref "L10") (pin "1") (pinfunction "1_1") (pintype "passive"))
    )
    (net (code "2") (name "/TCA_CLK1") (class "Default")
      (node (ref "C287") (pin "2") (pinfunction "2_2") (pintype "passive"))
      (node (ref "L16") (pin "1") (pinfunction "1_1") (pintype "passive"))
    )
    (net (code "3") (name "/TCA_CLK2") (class "Default")
      (node (ref "C295") (pin "2") (pinfunction "2_2") (pintype "passive"))
      (node (ref "L22") (pin "1") (pinfunction "1_1") (pintype "passive"))
    )
    (net (code "4") (name "/TCA_CLK3") (class "Default")
      (node (ref "C303") (pin "2") (pinfunction "2_2") (pintype "passive"))
      (node (ref "L28") (pin "1") (pinfunction "1_1") (pintype "passive"))
    )
    (net (code "5") (name "/TCA_CLK4") (class "Default")
      (node (ref "C311") (pin "2") (pinfunction "2_2") (pintype "passive"))
      (node (ref "L34") (pin "1") (pinfunction "1_1") (pintype "passive"))
    )
    (net (code "6") (name "/TCA_CLK5") (class "Default")
      (node (ref "C283") (pin "2") (pinfunction "2_2") (pintype "passive"))
      (node (ref "L13") (pin "1") (pinfunction "1_1") (pintype "passive"))
    )
    (net (code "7") (name "/TCA_CLK6") (class "Default")
      (node (ref "C291") (pin "2") (pinfunction "2_2") (pintype "passive"))
      (node (ref "L19") (pin "1") (pinfunction "1_1") (pintype "passive"))
    )
    (net (code "8") (name "/TCA_CLK7") (class "Default")
      (node (ref "C299") (pin "2") (pinfunction "2_2") (pintype "passive"))
      (node (ref "L25") (pin "1") (pinfunction "1_1") (pintype "passive"))
    )
    (net (code "9") (name "/TCA_CLK8") (class "Default")
      (node (ref "C307") (pin "2") (pinfunction "2_2") (pintype "passive"))
      (node (ref "L31") (pin "1") (pinfunction "1_1") (pintype "passive"))
    )
    (net (code "10") (name "/TC_SINUS_0") (class "Default")
      (node (ref "R261") (pin "2") (pinfunction "2_2") (pintype "passive"))
      (node (ref "R264") (pin "2") (pinfunction "2_2") (pintype "passive"))
    )
    (net (code "11") (name "/TC_SINUS_1") (class "Default")
      (node (ref "R267") (pin "2") (pinfunction "2_2") (pintype "passive"))
      (node (ref "R270") (pin "2") (pinfunction "2_2") (pintype "passive"))
    )
    (net (code "12") (name "/TC_SINUS_2") (class "Default")
      (node (ref "R273") (pin "2") (pinfunction "2_2") (pintype "passive"))
      (node (ref "R276") (pin "2") (pinfunction "2_2") (pintype "passive"))
    )
    (net (code "13") (name "/TC_SINUS_3") (class "Default")
      (node (ref "R279") (pin "2") (pinfunction "2_2") (pintype "passive"))
      (node (ref "R282") (pin "2") (pinfunction "2_2") (pintype "passive"))
    )
    (net (code "14") (name "/TC_SINUS_4") (class "Default")
      (node (ref "R285") (pin "2") (pinfunction "2_2") (pintype "passive"))
      (node (ref "R287") (pin "2") (pinfunction "2_2") (pintype "passive"))
    )
    (net (code "15") (name "/TC_SINUS_5") (class "Default")
      (node (ref "R262") (pin "2") (pinfunction "2_2") (pintype "passive"))
      (node (ref "R266") (pin "2") (pinfunction "2_2") (pintype "passive"))
    )
    (net (code "16") (name "/TC_SINUS_6") (class "Default")
      (node (ref "R268") (pin "2") (pinfunction "2_2") (pintype "passive"))
      (node (ref "R271") (pin "2") (pinfunction "2_2") (pintype "passive"))
    )
    (net (code "17") (name "/TC_SINUS_7") (class "Default")
      (node (ref "R274") (pin "2") (pinfunction "2_2") (pintype "passive"))
      (node (ref "R277") (pin "2") (pinfunction "2_2") (pintype "passive"))
    )
    (net (code "18") (name "/TC_SINUS_8") (class "Default")
      (node (ref "R280") (pin "2") (pinfunction "2_2") (pintype "passive"))
      (node (ref "R284") (pin "2") (pinfunction "2_2") (pintype "passive"))
    )
    (net (code "19") (name "Net-(C280-Pad2)") (class "Default")
      (node (ref "C280") (pin "2") (pinfunction "2_2") (pintype "passive"))
      (node (ref "L10") (pin "2") (pinfunction "2_2") (pintype "passive"))
      (node (ref "L11") (pin "1") (pinfunction "1_1") (pintype "passive"))
    )
    (net (code "20") (name "Net-(C281-Pad2)") (class "Default")
      (node (ref "C281") (pin "2") (pinfunction "2_2") (pintype "passive"))
      (node (ref "L11") (pin "2") (pinfunction "2_2") (pintype "passive"))
      (node (ref "L12") (pin "1") (pinfunction "1_1") (pintype "passive"))
    )
    (net (code "21") (name "Net-(C282-Pad2)") (class "Default")
      (node (ref "C282") (pin "2") (pinfunction "2_2") (pintype "passive"))
      (node (ref "L12") (pin "2") (pinfunction "2_2") (pintype "passive"))
      (node (ref "R261") (pin "1") (pinfunction "1_1") (pintype "passive"))
      (node (ref "R263") (pin "2") (pinfunction "2_2") (pintype "passive"))
    )
    (net (code "22") (name "Net-(C284-Pad2)") (class "Default")
      (node (ref "C284") (pin "2") (pinfunction "2_2") (pintype "passive"))
      (node (ref "L13") (pin "2") (pinfunction "2_2") (pintype "passive"))
      (node (ref "L14") (pin "1") (pinfunction "1_1") (pintype "passive"))
    )
    (net (code "23") (name "Net-(C285-Pad2)") (class "Default")
      (node (ref "C285") (pin "2") (pinfunction "2_2") (pintype "passive"))
      (node (ref "L14") (pin "2") (pinfunction "2_2") (pintype "passive"))
      (node (ref "L15") (pin "1") (pinfunction "1_1") (pintype "passive"))
    )
    (net (code "24") (name "Net-(C286-Pad2)") (class "Default")
      (node (ref "C286") (pin "2") (pinfunction "2_2") (pintype "passive"))
      (node (ref "L15") (pin "2") (pinfunction "2_2") (pintype "passive"))
      (node (ref "R262") (pin "1") (pinfunction "1_1") (pintype "passive"))
      (node (ref "R265") (pin "2") (pinfunction "2_2") (pintype "passive"))
    )
    (net (code "25") (name "Net-(C288-Pad2)") (class "Default")
      (node (ref "C288") (pin "2") (pinfunction "2_2") (pintype "passive"))
      (node (ref "L16") (pin "2") (pinfunction "2_2") (pintype "passive"))
      (node (ref "L17") (pin "1") (pinfunction "1_1") (pintype "passive"))
    )
    (net (code "26") (name "Net-(C289-Pad2)") (class "Default")
      (node (ref "C289") (pin "2") (pinfunction "2_2") (pintype "passive"))
      (node (ref "L17") (pin "2") (pinfunction "2_2") (pintype "passive"))
      (node (ref "L18") (pin "1") (pinfunction "1_1") (pintype "passive"))
    )
    (net (code "27") (name "Net-(C290-Pad2)") (class "Default")
      (node (ref "C290") (pin "2") (pinfunction "2_2") (pintype "passive"))
      (node (ref "L18") (pin "2") (pinfunction "2_2") (pintype "passive"))
      (node (ref "R267") (pin "1") (pinfunction "1_1") (pintype "passive"))
      (node (ref "R269") (pin "2") (pinfunction "2_2") (pintype "passive"))
    )
    (net (code "28") (name "Net-(C292-Pad2)") (class "Default")
      (node (ref "C292") (pin "2") (pinfunction "2_2") (pintype "passive"))
      (node (ref "L19") (pin "2") (pinfunction "2_2") (pintype "passive"))
      (node (ref "L20") (pin "1") (pinfunction "1_1") (pintype "passive"))
    )
    (net (code "29") (name "Net-(C293-Pad2)") (class "Default")
      (node (ref "C293") (pin "2") (pinfunction "2_2") (pintype "passive"))
      (node (ref "L20") (pin "2") (pinfunction "2_2") (pintype "passive"))
      (node (ref "L21") (pin "1") (pinfunction "1_1") (pintype "passive"))
    )
    (net (code "30") (name "Net-(C294-Pad2)") (class "Default")
      (node (ref "C294") (pin "2") (pinfunction "2_2") (pintype "passive"))
      (node (ref "L21") (pin "2") (pinfunction "2_2") (pintype "passive"))
      (node (ref "R268") (pin "1") (pinfunction "1_1") (pintype "passive"))
      (node (ref "R272") (pin "2") (pinfunction "2_2") (pintype "passive"))
    )
    (net (code "31") (name "Net-(C296-Pad2)") (class "Default")
      (node (ref "C296") (pin "2") (pinfunction "2_2") (pintype "passive"))
      (node (ref "L22") (pin "2") (pinfunction "2_2") (pintype "passive"))
      (node (ref "L23") (pin "1") (pinfunction "1_1") (pintype "passive"))
    )
    (net (code "32") (name "Net-(C297-Pad2)") (class "Default")
      (node (ref "C297") (pin "2") (pinfunction "2_2") (pintype "passive"))
      (node (ref "L23") (pin "2") (pinfunction "2_2") (pintype "passive"))
      (node (ref "L24") (pin "1") (pinfunction "1_1") (pintype "passive"))
    )
    (net (code "33") (name "Net-(C298-Pad2)") (class "Default")
      (node (ref "C298") (pin "2") (pinfunction "2_2") (pintype "passive"))
      (node (ref "L24") (pin "2") (pinfunction "2_2") (pintype "passive"))
      (node (ref "R273") (pin "1") (pinfunction "1_1") (pintype "passive"))
      (node (ref "R275") (pin "2") (pinfunction "2_2") (pintype "passive"))
    )
    (net (code "34") (name "Net-(C300-Pad2)") (class "Default")
      (node (ref "C300") (pin "2") (pinfunction "2_2") (pintype "passive"))
      (node (ref "L25") (pin "2") (pinfunction "2_2") (pintype "passive"))
      (node (ref "L26") (pin "1") (pinfunction "1_1") (pintype "passive"))
    )
    (net (code "35") (name "Net-(C301-Pad2)") (class "Default")
      (node (ref "C301") (pin "2") (pinfunction "2_2") (pintype "passive"))
      (node (ref "L26") (pin "2") (pinfunction "2_2") (pintype "passive"))
      (node (ref "L27") (pin "1") (pinfunction "1_1") (pintype "passive"))
    )
    (net (code "36") (name "Net-(C302-Pad2)") (class "Default")
      (node (ref "C302") (pin "2") (pinfunction "2_2") (pintype "passive"))
      (node (ref "L27") (pin "2") (pinfunction "2_2") (pintype "passive"))
      (node (ref "R274") (pin "1") (pinfunction "1_1") (pintype "passive"))
      (node (ref "R278") (pin "2") (pinfunction "2_2") (pintype "passive"))
    )
    (net (code "37") (name "Net-(C304-Pad2)") (class "Default")
      (node (ref "C304") (pin "2") (pinfunction "2_2") (pintype "passive"))
      (node (ref "L28") (pin "2") (pinfunction "2_2") (pintype "passive"))
      (node (ref "L29") (pin "1") (pinfunction "1_1") (pintype "passive"))
    )
    (net (code "38") (name "Net-(C305-Pad2)") (class "Default")
      (node (ref "C305") (pin "2") (pinfunction "2_2") (pintype "passive"))
      (node (ref "L29") (pin "2") (pinfunction "2_2") (pintype "passive"))
      (node (ref "L30") (pin "1") (pinfunction "1_1") (pintype "passive"))
    )
    (net (code "39") (name "Net-(C306-Pad2)") (class "Default")
      (node (ref "C306") (pin "2") (pinfunction "2_2") (pintype "passive"))
      (node (ref "L30") (pin "2") (pinfunction "2_2") (pintype "passive"))
      (node (ref "R279") (pin "1") (pinfunction "1_1") (pintype "passive"))
      (node (ref "R281") (pin "2") (pinfunction "2_2") (pintype "passive"))
    )
    (net (code "40") (name "Net-(C308-Pad2)") (class "Default")
      (node (ref "C308") (pin "2") (pinfunction "2_2") (pintype "passive"))
      (node (ref "L31") (pin "2") (pinfunction "2_2") (pintype "passive"))
      (node (ref "L32") (pin "1") (pinfunction "1_1") (pintype "passive"))
    )
    (net (code "41") (name "Net-(C309-Pad2)") (class "Default")
      (node (ref "C309") (pin "2") (pinfunction "2_2") (pintype "passive"))
      (node (ref "L32") (pin "2") (pinfunction "2_2") (pintype "passive"))
      (node (ref "L33") (pin "1") (pinfunction "1_1") (pintype "passive"))
    )
    (net (code "42") (name "Net-(C310-Pad2)") (class "Default")
      (node (ref "C310") (pin "2") (pinfunction "2_2") (pintype "passive"))
      (node (ref "L33") (pin "2") (pinfunction "2_2") (pintype "passive"))
      (node (ref "R280") (pin "1") (pinfunction "1_1") (pintype "passive"))
      (node (ref "R283") (pin "2") (pinfunction "2_2") (pintype "passive"))
    )
    (net (code "43") (name "Net-(C312-Pad2)") (class "Default")
      (node (ref "C312") (pin "2") (pinfunction "2_2") (pintype "passive"))
      (node (ref "L34") (pin "2") (pinfunction "2_2") (pintype "passive"))
      (node (ref "L35") (pin "1") (pinfunction "1_1") (pintype "passive"))
    )
    (net (code "44") (name "Net-(C313-Pad2)") (class "Default")
      (node (ref "C313") (pin "2") (pinfunction "2_2") (pintype "passive"))
      (node (ref "L35") (pin "2") (pinfunction "2_2") (pintype "passive"))
      (node (ref "L36") (pin "1") (pinfunction "1_1") (pintype "passive"))
    )
    (net (code "45") (name "Net-(C314-Pad2)") (class "Default")
      (node (ref "C314") (pin "2") (pinfunction "2_2") (pintype "passive"))
      (node (ref "L36") (pin "2") (pinfunction "2_2") (pintype "passive"))
      (node (ref "R285") (pin "1") (pinfunction "1_1") (pintype "passive"))
      (node (ref "R286") (pin "2") (pinfunction "2_2") (pintype "passive"))
    )
    (net (code "46") (name "TRB_GND") (class "Default")
      (node (ref "C279") (pin "1") (pinfunction "1_1") (pintype "passive"))
      (node (ref "C280") (pin "1") (pinfunction "1_1") (pintype "passive"))
      (node (ref "C281") (pin "1") (pinfunction "1_1") (pintype "passive"))
      (node (ref "C282") (pin "1") (pinfunction "1_1") (pintype "passive"))
      (node (ref "C283") (pin "1") (pinfunction "1_1") (pintype "passive"))
      (node (ref "C284") (pin "1") (pinfunction "1_1") (pintype "passive"))
      (node (ref "C285") (pin "1") (pinfunction "1_1") (pintype "passive"))
      (node (ref "C286") (pin "1") (pinfunction "1_1") (pintype "passive"))
      (node (ref "C287") (pin "1") (pinfunction "1_1") (pintype "passive"))
      (node (ref "C288") (pin "1") (pinfunction "1_1") (pintype "passive"))
      (node (ref "C289") (pin "1") (pinfunction "1_1") (pintype "passive"))
      (node (ref "C290") (pin "1") (pinfunction "1_1") (pintype "passive"))
      (node (ref "C291") (pin "1") (pinfunction "1_1") (pintype "passive"))
      (node (ref "C292") (pin "1") (pinfunction "1_1") (pintype "passive"))
      (node (ref "C293") (pin "1") (pinfunction "1_1") (pintype "passive"))
      (node (ref "C294") (pin "1") (pinfunction "1_1") (pintype "passive"))
      (node (ref "C295") (pin "1") (pinfunction "1_1") (pintype "passive"))
      (node (ref "C296") (pin "1") (pinfunction "1_1") (pintype "passive"))
      (node (ref "C297") (pin "1") (pinfunction "1_1") (pintype "passive"))
      (node (ref "C298") (pin "1") (pinfunction "1_1") (pintype "passive"))
      (node (ref "C299") (pin "1") (pinfunction "1_1") (pintype "passive"))
      (node (ref "C300") (pin "1") (pinfunction "1_1") (pintype "passive"))
      (node (ref "C301") (pin "1") (pinfunction "1_1") (pintype "passive"))
      (node (ref "C302") (pin "1") (pinfunction "1_1") (pintype "passive"))
      (node (ref "C303") (pin "1") (pinfunction "1_1") (pintype "passive"))
      (node (ref "C304") (pin "1") (pinfunction "1_1") (pintype "passive"))
      (node (ref "C305") (pin "1") (pinfunction "1_1") (pintype "passive"))
      (node (ref "C306") (pin "1") (pinfunction "1_1") (pintype "passive"))
      (node (ref "C307") (pin "1") (pinfunction "1_1") (pintype "passive"))
      (node (ref "C308") (pin "1") (pinfunction "1_1") (pintype "passive"))
      (node (ref "C309") (pin "1") (pinfunction "1_1") (pintype "passive"))
      (node (ref "C310") (pin "1") (pinfunction "1_1") (pintype "passive"))
      (node (ref "C311") (pin "1") (pinfunction "1_1") (pintype "passive"))
      (node (ref "C312") (pin "1") (pinfunction "1_1") (pintype "passive"))
      (node (ref "C313") (pin "1") (pinfunction "1_1") (pintype "passive"))
      (node (ref "C314") (pin "1") (pinfunction "1_1") (pintype "passive"))
      (node (ref "R263") (pin "1") (pinfunction "1_1") (pintype "passive"))
      (node (ref "R264") (pin "1") (pinfunction "1_1") (pintype "passive"))
      (node (ref "R265") (pin "1") (pinfunction "1_1") (pintype "passive"))
      (node (ref "R266") (pin "1") (pinfunction "1_1") (pintype "passive"))
      (node (ref "R269") (pin "1") (pinfunction "1_1") (pintype "passive"))
      (node (ref "R270") (pin "1") (pinfunction "1_1") (pintype "passive"))
      (node (ref "R271") (pin "1") (pinfunction "1_1") (pintype "passive"))
      (node (ref "R272") (pin "1") (pinfunction "1_1") (pintype "passive"))
      (node (ref "R275") (pin "1") (pinfunction "1_1") (pintype "passive"))
      (node (ref "R276") (pin "1") (pinfunction "1_1") (pintype "passive"))
      (node (ref "R277") (pin "1") (pinfunction "1_1") (pintype "passive"))
      (node (ref "R278") (pin "1") (pinfunction "1_1") (pintype "passive"))
      (node (ref "R281") (pin "1") (pinfunction "1_1") (pintype "passive"))
      (node (ref "R282") (pin "1") (pinfunction "1_1") (pintype "passive"))
      (node (ref "R283") (pin "1") (pinfunction "1_1") (pintype "passive"))
      (node (ref "R284") (pin "1") (pinfunction "1_1") (pintype "passive"))
      (node (ref "R286") (pin "1") (pinfunction "1_1") (pintype "passive"))
      (node (ref "R287") (pin "1") (pinfunction "1_1") (pintype "passive"))
    )
  )
)
